# PowerSupply.net
KiCad netlist of a schematic drawn in EAGLE
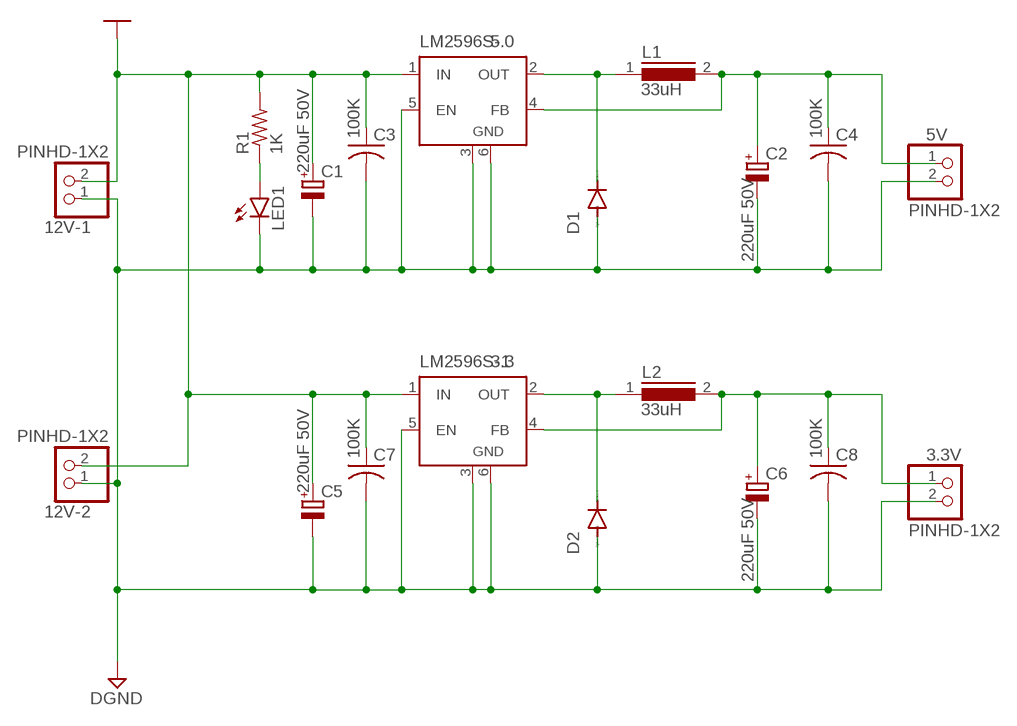
[diagram p0: schematic, sheet 1]

(export (version "E")
  (design (tool "Eeschema 10.0.6"))
  (components
    (comp (ref "3.3V")
      (value "PINHD-1X2")
      (footprint "eagle-import:1X02")
      (libsource (lib "eagle-import") (part "PINHD-1X2"))
    )
    (comp (ref "5V")
      (value "PINHD-1X2")
      (footprint "eagle-import:1X02")
      (libsource (lib "eagle-import") (part "PINHD-1X2"))
    )
    (comp (ref "12V-1")
      (value "PINHD-1X2")
      (footprint "eagle-import:1X02")
      (libsource (lib "eagle-import") (part "PINHD-1X2"))
    )
    (comp (ref "12V-2")
      (value "PINHD-1X2")
      (footprint "eagle-import:1X02")
      (libsource (lib "eagle-import") (part "PINHD-1X2"))
    )
    (comp (ref "C1")
      (value "220uF 50V")
      (footprint "eagle-import:CAPAE1030X1050N")
      (libsource (lib "eagle-import") (part "C-POLECAP-10.5MM_"))
    )
    (comp (ref "C2")
      (value "220uF 50V")
      (footprint "eagle-import:CAPAE1030X1050N")
      (libsource (lib "eagle-import") (part "C-POLECAP-10.5MM_"))
    )
    (comp (ref "C3")
      (value "100K")
      (footprint "eagle-import:CAPC3216X135")
      (libsource (lib "eagle-import") (part "C-USCHIP-1206(3216-METRIC)_"))
    )
    (comp (ref "C4")
      (value "100K")
      (footprint "eagle-import:CAPC3216X135")
      (libsource (lib "eagle-import") (part "C-USCHIP-1206(3216-METRIC)_"))
    )
    (comp (ref "C5")
      (value "220uF 50V")
      (footprint "eagle-import:CAPAE1030X1050N")
      (libsource (lib "eagle-import") (part "C-POLECAP-10.5MM_"))
    )
    (comp (ref "C6")
      (value "220uF 50V")
      (footprint "eagle-import:CAPAE1030X1050N")
      (libsource (lib "eagle-import") (part "C-POLECAP-10.5MM_"))
    )
    (comp (ref "C7")
      (value "100K")
      (footprint "eagle-import:CAPC3216X135")
      (libsource (lib "eagle-import") (part "C-USCHIP-1206(3216-METRIC)_"))
    )
    (comp (ref "C8")
      (value "100K")
      (footprint "eagle-import:CAPC3216X135")
      (libsource (lib "eagle-import") (part "C-USCHIP-1206(3216-METRIC)_"))
    )
    (comp (ref "D1")
      (value "DIODE-DO214AA")
      (footprint "eagle-import:DO214AA")
      (libsource (lib "eagle-import") (part "DIODE-DO214AA"))
    )
    (comp (ref "D2")
      (value "DIODE-DO214AA")
      (footprint "eagle-import:DO214AA")
      (libsource (lib "eagle-import") (part "DIODE-DO214AA"))
    )
    (comp (ref "L1")
      (value "33uH")
      (footprint "eagle-import:SRR1210")
      (libsource (lib "eagle-import") (part "SRR1210"))
    )
    (comp (ref "L2")
      (value "33uH")
      (footprint "eagle-import:SRR1210")
      (libsource (lib "eagle-import") (part "SRR1210"))
    )
    (comp (ref "LED1")
      (value "LEDCHIPLED_1206")
      (footprint "eagle-import:CHIPLED_1206")
      (libsource (lib "eagle-import") (part "LEDCHIPLED_1206"))
    )
    (comp (ref "LM2596S-")
      (value "5.0")
      (footprint "eagle-import:TO263-5")
      (libsource (lib "eagle-import") (part "LM2596S"))
    )
    (comp (ref "LM2596S-1")
      (value "3.3")
      (footprint "eagle-import:TO263-5")
      (libsource (lib "eagle-import") (part "LM2596S"))
    )
    (comp (ref "R1")
      (value "1K")
      (footprint "eagle-import:R1206")
      (libsource (lib "eagle-import") (part "R-US_R1206"))
    )
  )
  (nets
    (net (code "1") (name "DGND") (class "Default")
      (node (ref "12V-1") (pin "1") (pinfunction "1_1") (pintype "passive"))
      (node (ref "12V-2") (pin "1") (pinfunction "1_1") (pintype "passive"))
      (node (ref "3.3V") (pin "2") (pinfunction "2_2") (pintype "passive"))
      (node (ref "5V") (pin "2") (pinfunction "2_2") (pintype "passive"))
      (node (ref "C1") (pin "2") (pinfunction "-_2") (pintype "passive"))
      (node (ref "C2") (pin "2") (pinfunction "-_2") (pintype "passive"))
      (node (ref "C3") (pin "2") (pinfunction "2_2") (pintype "passive"))
      (node (ref "C4") (pin "2") (pinfunction "2_2") (pintype "passive"))
      (node (ref "C5") (pin "2") (pinfunction "-_2") (pintype "passive"))
      (node (ref "C6") (pin "2") (pinfunction "-_2") (pintype "passive"))
      (node (ref "C7") (pin "2") (pinfunction "2_2") (pintype "passive"))
      (node (ref "C8") (pin "2") (pinfunction "2_2") (pintype "passive"))
      (node (ref "D1") (pin "A") (pinfunction "A_A") (pintype "passive"))
      (node (ref "D2") (pin "A") (pinfunction "A_A") (pintype "passive"))
      (node (ref "LED1") (pin "C") (pinfunction "C_C") (pintype "passive"))
      (node (ref "LM2596S-") (pin "3") (pinfunction "GND_3") (pintype "power_in"))
      (node (ref "LM2596S-") (pin "5") (pinfunction "EN_5") (pintype "input"))
      (node (ref "LM2596S-") (pin "6") (pinfunction "GND_6") (pintype "power_in"))
      (node (ref "LM2596S-1") (pin "3") (pinfunction "GND_3") (pintype "power_in"))
      (node (ref "LM2596S-1") (pin "5") (pinfunction "EN_5") (pintype "input"))
      (node (ref "LM2596S-1") (pin "6") (pinfunction "GND_6") (pintype "power_in"))
    )
    (net (code "2") (name "Net-(C2-+)") (class "Default")
      (node (ref "5V") (pin "1") (pinfunction "1_1") (pintype "passive"))
      (node (ref "C2") (pin "1") (pinfunction "+_1") (pintype "passive"))
      (node (ref "C4") (pin "1") (pinfunction "1_1") (pintype "passive"))
      (node (ref "L1") (pin "2") (pinfunction "2_2") (pintype "passive"))
      (node (ref "LM2596S-") (pin "4") (pinfunction "FB_4") (pintype "input"))
    )
    (net (code "3") (name "Net-(C6-+)") (class "Default")
      (node (ref "3.3V") (pin "1") (pinfunction "1_1") (pintype "passive"))
      (node (ref "C6") (pin "1") (pinfunction "+_1") (pintype "passive"))
      (node (ref "C8") (pin "1") (pinfunction "1_1") (pintype "passive"))
      (node (ref "L2") (pin "2") (pinfunction "2_2") (pintype "passive"))
      (node (ref "LM2596S-1") (pin "4") (pinfunction "FB_4") (pintype "input"))
    )
    (net (code "4") (name "Net-(LED1-PadA)") (class "Default")
      (node (ref "LED1") (pin "A") (pinfunction "A_A") (pintype "passive"))
      (node (ref "R1") (pin "1") (pinfunction "1_1") (pintype "passive"))
    )
    (net (code "5") (name "Net-(LM2596S--OUT)") (class "Default")
      (node (ref "D1") (pin "C") (pinfunction "C_C") (pintype "passive"))
      (node (ref "L1") (pin "1") (pinfunction "1_1") (pintype "passive"))
      (node (ref "LM2596S-") (pin "2") (pinfunction "OUT_2") (pintype "output"))
    )
    (net (code "6") (name "Net-(LM2596S-1-OUT)") (class "Default")
      (node (ref "D2") (pin "C") (pinfunction "C_C") (pintype "passive"))
      (node (ref "L2") (pin "1") (pinfunction "1_1") (pintype "passive"))
      (node (ref "LM2596S-1") (pin "2") (pinfunction "OUT_2") (pintype "output"))
    )
    (net (code "7") (name "VCC") (class "Default")
      (node (ref "12V-1") (pin "2") (pinfunction "2_2") (pintype "passive"))
      (node (ref "12V-2") (pin "2") (pinfunction "2_2") (pintype "passive"))
      (node (ref "C1") (pin "1") (pinfunction "+_1") (pintype "passive"))
      (node (ref "C3") (pin "1") (pinfunction "1_1") (pintype "passive"))
      (node (ref "C5") (pin "1") (pinfunction "+_1") (pintype "passive"))
      (node (ref "C7") (pin "1") (pinfunction "1_1") (pintype "passive"))
      (node (ref "LM2596S-") (pin "1") (pinfunction "IN_1") (pintype "input"))
      (node (ref "LM2596S-1") (pin "1") (pinfunction "IN_1") (pintype "input"))
      (node (ref "R1") (pin "2") (pinfunction "2_2") (pintype "passive"))
    )
  )
)
